# USB.net
KiCad netlist of a schematic drawn in Altium Designer
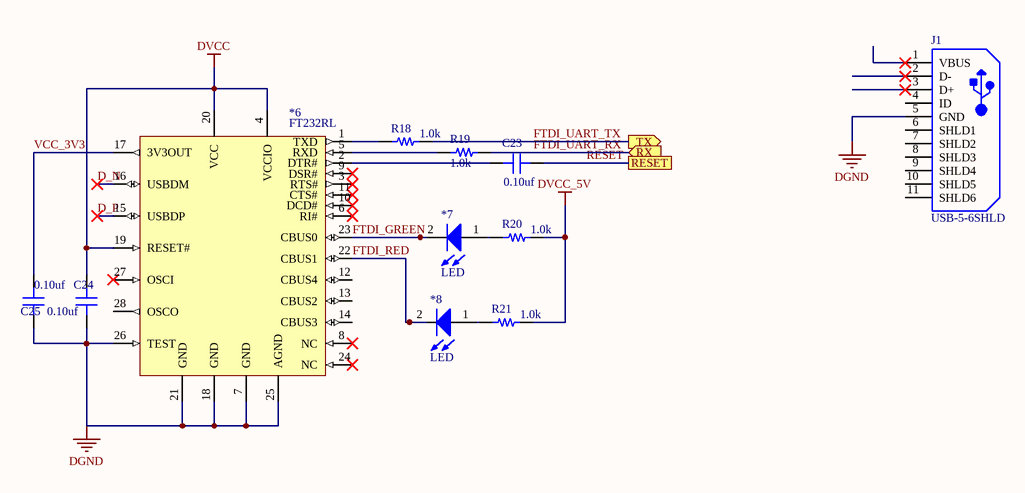
[diagram p0: USB.SchDoc]

(export (version "E")
  (design (tool "Eeschema 10.0.6"))
  (components
    (comp (ref "*6")
      (value "FT232RL")
      (footprint "SSOP-28")
      (fields (field (name "CREATED_BY") "Kyle"))
      (libsource (lib "Altium-Lib") (part "FT232RL"))
    )
    (comp (ref "*7") (value "LED") (footprint "0805_LED") (libsource (lib "Altium-Lib") (part "LED")))
    (comp (ref "*8") (value "LED") (footprint "0805_LED") (libsource (lib "Altium-Lib") (part "LED")))
    (comp (ref "C23")
      (value "0.10uf")
      (footprint "CAP 0603/1608")
      (fields
        (field (name "Comment") "Capacitor MLCC 0.10uf 25V CAP 0603/1608")
        (field (name "CREATED_BY") "Nick Mah")
      )
      (libsource (lib "Altium-Lib") (part "Capacitor"))
    )
    (comp (ref "C24")
      (value "0.10uf")
      (footprint "CAP 0603/1608")
      (fields
        (field (name "Comment") "Capacitor MLCC 0.10uf 25V CAP 0603/1608")
        (field (name "CREATED_BY") "Nick Mah")
      )
      (libsource (lib "Altium-Lib") (part "Capacitor"))
    )
    (comp (ref "C25")
      (value "0.10uf")
      (footprint "CAP 0603/1608")
      (fields
        (field (name "Comment") "Capacitor MLCC 0.10uf 25V CAP 0603/1608")
        (field (name "CREATED_BY") "Nick Mah")
      )
      (libsource (lib "Altium-Lib") (part "Capacitor"))
    )
    (comp (ref "J1")
      (value "USB-5-6SHLD")
      (footprint "TECO-1981568-5_V")
      (description "USB Micro Type B")
      (fields (field (name "MFRPARTNO") "1981568-1") (field (name "CREATED_BY") "Aiku"))
      (libsource (lib "Altium-Lib") (part "USB-5-6SHLD"))
    )
    (comp (ref "R18")
      (value "1.0k")
      (footprint "RES 0805/2012")
      (fields
        (field (name "TOLERANCE") "1%")
        (field (name "POWER") "1/4W")
        (field (name "Comment") "Resistor 1.0k 0805 1/4W 1%")
        (field (name "CREATED_BY") "Nick Mah")
      )
      (libsource (lib "Altium-Lib") (part "Resistor"))
    )
    (comp (ref "R19")
      (value "1.0k")
      (footprint "RES 0805/2012")
      (fields
        (field (name "TOLERANCE") "1%")
        (field (name "POWER") "1/4W")
        (field (name "Comment") "Resistor 1.0k 0805 1/4W 1%")
        (field (name "CREATED_BY") "Nick Mah")
      )
      (libsource (lib "Altium-Lib") (part "Resistor"))
    )
    (comp (ref "R20")
      (value "1.0k")
      (footprint "RES 0805/2012")
      (fields
        (field (name "TOLERANCE") "1%")
        (field (name "POWER") "1/4W")
        (field (name "Comment") "Resistor 1.0k 0805 1/4W 1%")
        (field (name "CREATED_BY") "Nick Mah")
      )
      (libsource (lib "Altium-Lib") (part "Resistor"))
    )
    (comp (ref "R21")
      (value "1.0k")
      (footprint "RES 0805/2012")
      (fields
        (field (name "TOLERANCE") "1%")
        (field (name "POWER") "1/4W")
        (field (name "Comment") "Resistor 1.0k 0805 1/4W 1%")
        (field (name "CREATED_BY") "Nick Mah")
      )
      (libsource (lib "Altium-Lib") (part "Resistor"))
    )
  )
  (nets
    (net (code "1") (name "/D_N") (class "Default")
      (node (ref "*6") (pin "16") (pinfunction "USBDM_16") (pintype "bidirectional+no_connect"))
    )
    (net (code "2") (name "/D_P") (class "Default")
      (node (ref "*6") (pin "15") (pinfunction "USBDP_15") (pintype "bidirectional+no_connect"))
    )
    (net (code "3") (name "/FTDI_GREEN") (class "Default")
      (node (ref "*6") (pin "23") (pinfunction "CBUS0_23") (pintype "bidirectional"))
      (node (ref "*7") (pin "2") (pinfunction "K_2") (pintype "passive"))
    )
    (net (code "4") (name "/FTDI_RED") (class "Default")
      (node (ref "*6") (pin "22") (pinfunction "CBUS1_22") (pintype "bidirectional"))
      (node (ref "*8") (pin "2") (pinfunction "K_2") (pintype "passive"))
    )
    (net (code "5") (name "/FTDI_UART_RX") (class "Default")
      (node (ref "R19") (pin "2") (pinfunction "2_2") (pintype "passive"))
    )
    (net (code "6") (name "/FTDI_UART_TX") (class "Default")
      (node (ref "R18") (pin "2") (pinfunction "2_2") (pintype "passive"))
    )
    (net (code "7") (name "/RESET") (class "Default")
      (node (ref "C23") (pin "2") (pinfunction "2_2") (pintype "passive"))
    )
    (net (code "8") (name "/VCC_3V3") (class "Default")
      (node (ref "*6") (pin "17") (pinfunction "3V3OUT_17") (pintype "output"))
      (node (ref "C25") (pin "2") (pinfunction "2_2") (pintype "passive"))
    )
    (net (code "9") (name "DGND") (class "Default")
      (node (ref "*6") (pin "18") (pinfunction "GND_18") (pintype "passive"))
      (node (ref "*6") (pin "21") (pinfunction "GND_21") (pintype "passive"))
      (node (ref "*6") (pin "25") (pinfunction "AGND_25") (pintype "passive"))
      (node (ref "*6") (pin "26") (pinfunction "TEST_26") (pintype "input"))
      (node (ref "*6") (pin "7") (pinfunction "GND_7") (pintype "passive"))
      (node (ref "C24") (pin "1") (pinfunction "1_1") (pintype "passive"))
      (node (ref "C25") (pin "1") (pinfunction "1_1") (pintype "passive"))
      (node (ref "J1") (pin "5") (pinfunction "GND_5") (pintype "passive"))
    )
    (net (code "10") (name "DVCC") (class "Default")
      (node (ref "*6") (pin "19") (pinfunction "RESET#_19") (pintype "input"))
      (node (ref "*6") (pin "20") (pinfunction "VCC_20") (pintype "passive"))
      (node (ref "*6") (pin "4") (pinfunction "VCCIO_4") (pintype "passive"))
      (node (ref "C24") (pin "2") (pinfunction "2_2") (pintype "passive"))
    )
    (net (code "11") (name "DVCC_5V") (class "Default")
      (node (ref "R20") (pin "2") (pinfunction "2_2") (pintype "passive"))
      (node (ref "R21") (pin "2") (pinfunction "2_2") (pintype "passive"))
    )
    (net (code "12") (name "Net-(*6-DTR#)") (class "Default")
      (node (ref "*6") (pin "2") (pinfunction "DTR#_2") (pintype "output"))
      (node (ref "C23") (pin "1") (pinfunction "1_1") (pintype "passive"))
    )
    (net (code "13") (name "Net-(*6-RXD)") (class "Default")
      (node (ref "*6") (pin "5") (pinfunction "RXD_5") (pintype "input"))
      (node (ref "R19") (pin "1") (pinfunction "1_1") (pintype "passive"))
    )
    (net (code "14") (name "Net-(*6-TXD)") (class "Default")
      (node (ref "*6") (pin "1") (pinfunction "TXD_1") (pintype "output"))
      (node (ref "R18") (pin "1") (pinfunction "1_1") (pintype "passive"))
    )
    (net (code "15") (name "Net-(*7-A)") (class "Default")
      (node (ref "*7") (pin "1") (pinfunction "A_1") (pintype "passive"))
      (node (ref "R20") (pin "1") (pinfunction "1_1") (pintype "passive"))
    )
    (net (code "16") (name "Net-(*8-A)") (class "Default")
      (node (ref "*8") (pin "1") (pinfunction "A_1") (pintype "passive"))
      (node (ref "R21") (pin "1") (pinfunction "1_1") (pintype "passive"))
    )
    (net (code "17") (name "unconnected-(*6-CBUS2-Pad13)") (class "Default")
      (node (ref "*6") (pin "13") (pinfunction "CBUS2_13") (pintype "bidirectional"))
    )
    (net (code "18") (name "unconnected-(*6-CBUS3-Pad14)") (class "Default")
      (node (ref "*6") (pin "14") (pinfunction "CBUS3_14") (pintype "bidirectional"))
    )
    (net (code "19") (name "unconnected-(*6-CBUS4-Pad12)") (class "Default")
      (node (ref "*6") (pin "12") (pinfunction "CBUS4_12") (pintype "bidirectional"))
    )
    (net (code "20") (name "unconnected-(*6-CTS#-Pad11)") (class "Default")
      (node (ref "*6") (pin "11") (pinfunction "CTS#_11") (pintype "input+no_connect"))
    )
    (net (code "21") (name "unconnected-(*6-DCD#-Pad10)") (class "Default")
      (node (ref "*6") (pin "10") (pinfunction "DCD#_10") (pintype "input+no_connect"))
    )
    (net (code "22") (name "unconnected-(*6-DSR#-Pad9)") (class "Default")
      (node (ref "*6") (pin "9") (pinfunction "DSR#_9") (pintype "input+no_connect"))
    )
    (net (code "23") (name "unconnected-(*6-NC-Pad8)") (class "Default")
      (node (ref "*6") (pin "8") (pinfunction "NC_8") (pintype "input+no_connect"))
    )
    (net (code "24") (name "unconnected-(*6-NC-Pad24)") (class "Default")
      (node (ref "*6") (pin "24") (pinfunction "NC_24") (pintype "input+no_connect"))
    )
    (net (code "25") (name "unconnected-(*6-OSCI-Pad27)") (class "Default")
      (node (ref "*6") (pin "27") (pinfunction "OSCI_27") (pintype "input+no_connect"))
    )
    (net (code "26") (name "unconnected-(*6-OSCO-Pad28)") (class "Default")
      (node (ref "*6") (pin "28") (pinfunction "OSCO_28") (pintype "output"))
    )
    (net (code "27") (name "unconnected-(*6-RI#-Pad6)") (class "Default")
      (node (ref "*6") (pin "6") (pinfunction "RI#_6") (pintype "input+no_connect"))
    )
    (net (code "28") (name "unconnected-(*6-RTS#-Pad3)") (class "Default")
      (node (ref "*6") (pin "3") (pinfunction "RTS#_3") (pintype "output+no_connect"))
    )
    (net (code "29") (name "unconnected-(J1-D+-Pad3)") (class "Default")
      (node (ref "J1") (pin "3") (pinfunction "D+_3") (pintype "passive+no_connect"))
    )
    (net (code "30") (name "unconnected-(J1-D--Pad2)") (class "Default")
      (node (ref "J1") (pin "2") (pinfunction "D-_2") (pintype "passive+no_connect"))
    )
    (net (code "31") (name "unconnected-(J1-ID-Pad4)") (class "Default")
      (node (ref "J1") (pin "4") (pinfunction "ID_4") (pintype "passive"))
    )
    (net (code "32") (name "unconnected-(J1-SHLD1-Pad6)") (class "Default")
      (node (ref "J1") (pin "6") (pinfunction "SHLD1_6") (pintype "passive"))
    )
    (net (code "33") (name "unconnected-(J1-SHLD2-Pad7)") (class "Default")
      (node (ref "J1") (pin "7") (pinfunction "SHLD2_7") (pintype "passive"))
    )
    (net (code "34") (name "unconnected-(J1-SHLD3-Pad8)") (class "Default")
      (node (ref "J1") (pin "8") (pinfunction "SHLD3_8") (pintype "passive"))
    )
    (net (code "35") (name "unconnected-(J1-SHLD4-Pad9)") (class "Default")
      (node (ref "J1") (pin "9") (pinfunction "SHLD4_9") (pintype "passive"))
    )
    (net (code "36") (name "unconnected-(J1-SHLD5-Pad10)") (class "Default")
      (node (ref "J1") (pin "10") (pinfunction "SHLD5_10") (pintype "passive"))
    )
    (net (code "37") (name "unconnected-(J1-SHLD6-Pad11)") (class "Default")
      (node (ref "J1") (pin "11") (pinfunction "SHLD6_11") (pintype "passive"))
    )
    (net (code "38") (name "unconnected-(J1-VBUS-Pad1)") (class "Default")
      (node (ref "J1") (pin "1") (pinfunction "VBUS_1") (pintype "passive+no_connect"))
    )
  )
)
